# FetController.net
KiCad netlist of a schematic drawn in Altium Designer
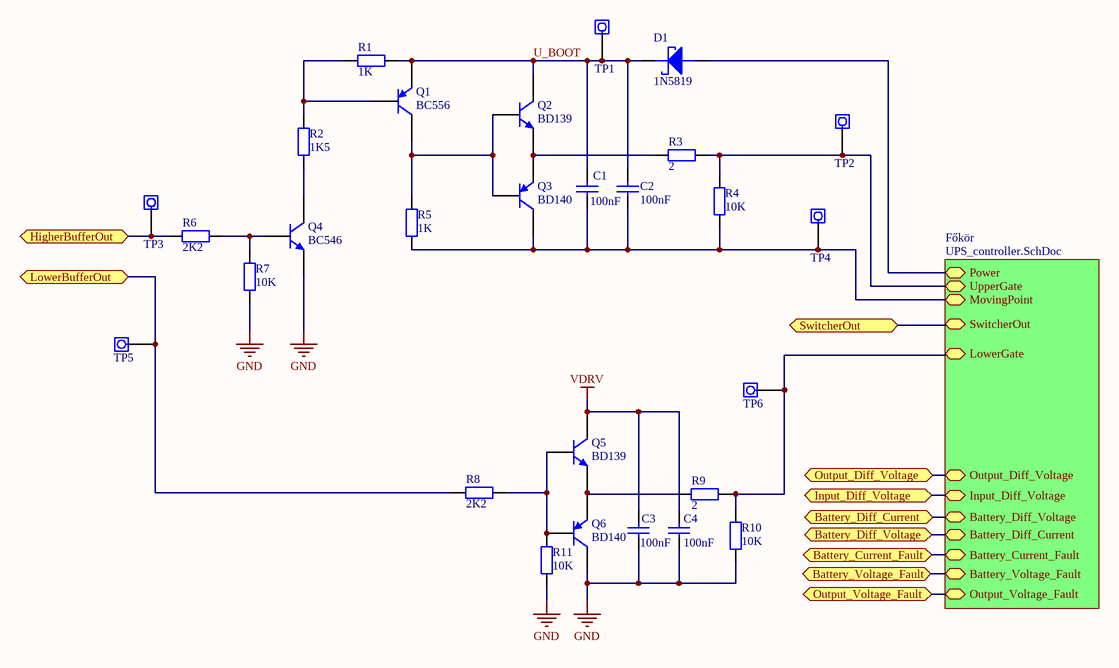
[diagram p0: FetController.SchDoc]

(export (version "E")
  (design (tool "Eeschema 10.0.6"))
  (components
    (comp (ref "C1")
      (value "100nF")
      (footprint "FP_0805_CAP_085")
      (description "Capacitor")
      (libsource (lib "hallglib") (part "CAP"))
    )
    (comp (ref "C2")
      (value "100nF")
      (footprint "FP_0805_CAP_085")
      (description "Capacitor")
      (libsource (lib "hallglib") (part "CAP"))
    )
    (comp (ref "C3")
      (value "100nF")
      (footprint "FP_0805_CAP_085")
      (description "Capacitor")
      (libsource (lib "hallglib") (part "CAP"))
    )
    (comp (ref "C4")
      (value "100nF")
      (footprint "FP_0805_CAP_085")
      (description "Capacitor")
      (libsource (lib "hallglib") (part "CAP"))
    )
    (comp (ref "D1")
      (value "1N5819")
      (footprint "AXIAL-0.3")
      (description "NXP - PMEG3020EJ,115 - SCHOTTKY RECT 30V 2A SOD323F")
      (libsource (lib "hallglib") (part "SCHOTTKY"))
    )
    (comp (ref "Q1")
      (value "BC556")
      (footprint "TO-92")
      (description "PNP tranzisztor")
      (libsource (lib "hallglib") (part "BC556"))
    )
    (comp (ref "Q2")
      (value "BD139")
      (footprint "TO-32")
      (description "NPN tranzisztor")
      (libsource (lib "hallglib") (part "BD139"))
    )
    (comp (ref "Q3")
      (value "BD140")
      (footprint "TO-32")
      (description "PNP tranzisztor")
      (libsource (lib "hallglib") (part "BD140"))
    )
    (comp (ref "Q4")
      (value "BC546")
      (footprint "TO-92")
      (description "NPN tranzisztor")
      (libsource (lib "hallglib") (part "BC546"))
    )
    (comp (ref "Q5")
      (value "BD139")
      (footprint "TO-32")
      (description "NPN tranzisztor")
      (libsource (lib "hallglib") (part "BD139"))
    )
    (comp (ref "Q6")
      (value "BD140")
      (footprint "TO-32")
      (description "PNP tranzisztor")
      (libsource (lib "hallglib") (part "BD140"))
    )
    (comp (ref "R1")
      (value "1K")
      (footprint "AXIAL-0.3")
      (description "Resistor")
      (libsource (lib "") (part "RES_2"))
    )
    (comp (ref "R2")
      (value "1K5")
      (footprint "AXIAL-0.3")
      (description "Resistor")
      (libsource (lib "hallglib") (part "RES"))
    )
    (comp (ref "R3")
      (value "2")
      (footprint "AXIAL-0.3")
      (description "Resistor")
      (libsource (lib "") (part "RES_1"))
    )
    (comp (ref "R4")
      (value "10K")
      (footprint "AXIAL-0.3")
      (description "Resistor")
      (libsource (lib "hallglib") (part "RES"))
    )
    (comp (ref "R5")
      (value "1K")
      (footprint "AXIAL-0.3")
      (description "Resistor")
      (libsource (lib "hallglib") (part "RES"))
    )
    (comp (ref "R6")
      (value "2K2")
      (footprint "AXIAL-0.3")
      (description "Resistor")
      (libsource (lib "") (part "RES_2"))
    )
    (comp (ref "R7")
      (value "10K")
      (footprint "AXIAL-0.3")
      (description "Resistor")
      (libsource (lib "hallglib") (part "RES"))
    )
    (comp (ref "R8")
      (value "2K2")
      (footprint "AXIAL-0.3")
      (description "Resistor")
      (libsource (lib "") (part "RES_2"))
    )
    (comp (ref "R9")
      (value "2")
      (footprint "AXIAL-0.3")
      (description "Resistor")
      (libsource (lib "") (part "RES_1"))
    )
    (comp (ref "R10")
      (value "10K")
      (footprint "AXIAL-0.3")
      (description "Resistor")
      (libsource (lib "hallglib") (part "RES"))
    )
    (comp (ref "R11")
      (value "10K")
      (footprint "AXIAL-0.3")
      (description "Resistor")
      (libsource (lib "hallglib") (part "RES"))
    )
    (comp (ref "TP1")
      (value "Testpoint")
      (footprint "TESTPOINT_1.5")
      (libsource (lib "MERES") (part "Testpoint"))
    )
    (comp (ref "TP2")
      (value "Testpoint")
      (footprint "TESTPOINT_1.5")
      (libsource (lib "MERES") (part "Testpoint"))
    )
    (comp (ref "TP3")
      (value "Testpoint")
      (footprint "TESTPOINT_1.5")
      (libsource (lib "MERES") (part "Testpoint"))
    )
    (comp (ref "TP4")
      (value "Testpoint")
      (footprint "TESTPOINT_1.5")
      (libsource (lib "MERES") (part "Testpoint"))
    )
    (comp (ref "TP5")
      (value "Testpoint")
      (footprint "TESTPOINT_1.5")
      (libsource (lib "MERES") (part "Testpoint"))
    )
    (comp (ref "TP6")
      (value "Testpoint")
      (footprint "TESTPOINT_1.5")
      (libsource (lib "MERES") (part "Testpoint"))
    )
  )
  (nets
    (net (code "5") (name "/HigherBufferOut") (class "Default")
      (node (ref "R6") (pin "2") (pinfunction "2_2") (pintype "passive"))
      (node (ref "TP3") (pin "1") (pinfunction "1_1") (pintype "passive"))
    )
    (net (code "7") (name "/LowerBufferOut") (class "Default")
      (node (ref "R8") (pin "2") (pinfunction "2_2") (pintype "passive"))
      (node (ref "TP5") (pin "1") (pinfunction "1_1") (pintype "passive"))
    )
    (net (code "8") (name "/LowerGate") (class "Default")
      (node (ref "R10") (pin "2") (pinfunction "2_2") (pintype "passive"))
      (node (ref "R9") (pin "2") (pinfunction "2_2") (pintype "passive"))
      (node (ref "TP6") (pin "1") (pinfunction "1_1") (pintype "passive"))
    )
    (net (code "9") (name "/MovingPoint") (class "Default")
      (node (ref "C1") (pin "1") (pinfunction "1_1") (pintype "passive"))
      (node (ref "C2") (pin "1") (pinfunction "1_1") (pintype "passive"))
      (node (ref "Q3") (pin "2") (pinfunction "C_2") (pintype "passive"))
      (node (ref "R4") (pin "1") (pinfunction "1_1") (pintype "passive"))
      (node (ref "R5") (pin "1") (pinfunction "1_1") (pintype "passive"))
      (node (ref "TP4") (pin "1") (pinfunction "1_1") (pintype "passive"))
    )
    (net (code "12") (name "/Power") (class "Default")
      (node (ref "D1") (pin "2") (pinfunction "ANODE_2") (pintype "passive"))
    )
    (net (code "14") (name "/U_BOOT") (class "Default")
      (node (ref "C1") (pin "2") (pinfunction "2_2") (pintype "passive"))
      (node (ref "C2") (pin "2") (pinfunction "2_2") (pintype "passive"))
      (node (ref "D1") (pin "1") (pinfunction "CATHODE_1") (pintype "passive"))
      (node (ref "Q1") (pin "3") (pinfunction "E_3") (pintype "passive"))
      (node (ref "Q2") (pin "2") (pinfunction "C_2") (pintype "passive"))
      (node (ref "R1") (pin "1") (pinfunction "1_1") (pintype "passive"))
      (node (ref "TP1") (pin "1") (pinfunction "1_1") (pintype "passive"))
    )
    (net (code "15") (name "/UpperGate") (class "Default")
      (node (ref "R3") (pin "2") (pinfunction "2_2") (pintype "passive"))
      (node (ref "R4") (pin "2") (pinfunction "2_2") (pintype "passive"))
      (node (ref "TP2") (pin "1") (pinfunction "1_1") (pintype "passive"))
    )
    (net (code "16") (name "GND") (class "Default")
      (node (ref "C3") (pin "1") (pinfunction "1_1") (pintype "passive"))
      (node (ref "C4") (pin "1") (pinfunction "1_1") (pintype "passive"))
      (node (ref "Q4") (pin "3") (pinfunction "E_3") (pintype "passive"))
      (node (ref "Q6") (pin "2") (pinfunction "C_2") (pintype "passive"))
      (node (ref "R10") (pin "1") (pinfunction "1_1") (pintype "passive"))
      (node (ref "R11") (pin "1") (pinfunction "1_1") (pintype "passive"))
      (node (ref "R7") (pin "1") (pinfunction "1_1") (pintype "passive"))
    )
    (net (code "17") (name "Net-(Q1-B)") (class "Default")
      (node (ref "Q1") (pin "2") (pinfunction "B_2") (pintype "passive"))
      (node (ref "R1") (pin "2") (pinfunction "2_2") (pintype "passive"))
      (node (ref "R2") (pin "2") (pinfunction "2_2") (pintype "passive"))
    )
    (net (code "18") (name "Net-(Q1-C)") (class "Default")
      (node (ref "Q1") (pin "1") (pinfunction "C_1") (pintype "passive"))
      (node (ref "Q2") (pin "3") (pinfunction "B_3") (pintype "passive"))
      (node (ref "Q3") (pin "1") (pinfunction "B_1") (pintype "passive"))
      (node (ref "R5") (pin "2") (pinfunction "2_2") (pintype "passive"))
    )
    (net (code "19") (name "Net-(Q2-E)") (class "Default")
      (node (ref "Q2") (pin "1") (pinfunction "E_1") (pintype "passive"))
      (node (ref "Q3") (pin "3") (pinfunction "E_3") (pintype "passive"))
      (node (ref "R3") (pin "1") (pinfunction "1_1") (pintype "passive"))
    )
    (net (code "20") (name "Net-(Q4-B)") (class "Default")
      (node (ref "Q4") (pin "2") (pinfunction "B_2") (pintype "passive"))
      (node (ref "R6") (pin "1") (pinfunction "1_1") (pintype "passive"))
      (node (ref "R7") (pin "2") (pinfunction "2_2") (pintype "passive"))
    )
    (net (code "21") (name "Net-(Q4-C)") (class "Default")
      (node (ref "Q4") (pin "1") (pinfunction "C_1") (pintype "passive"))
      (node (ref "R2") (pin "1") (pinfunction "1_1") (pintype "passive"))
    )
    (net (code "22") (name "Net-(Q5-B)") (class "Default")
      (node (ref "Q5") (pin "3") (pinfunction "B_3") (pintype "passive"))
      (node (ref "Q6") (pin "1") (pinfunction "B_1") (pintype "passive"))
      (node (ref "R11") (pin "2") (pinfunction "2_2") (pintype "passive"))
      (node (ref "R8") (pin "1") (pinfunction "1_1") (pintype "passive"))
    )
    (net (code "23") (name "Net-(Q5-E)") (class "Default")
      (node (ref "Q5") (pin "1") (pinfunction "E_1") (pintype "passive"))
      (node (ref "Q6") (pin "3") (pinfunction "E_3") (pintype "passive"))
      (node (ref "R9") (pin "1") (pinfunction "1_1") (pintype "passive"))
    )
    (net (code "24") (name "VDRV") (class "Default")
      (node (ref "C3") (pin "2") (pinfunction "2_2") (pintype "passive"))
      (node (ref "C4") (pin "2") (pinfunction "2_2") (pintype "passive"))
      (node (ref "Q5") (pin "2") (pinfunction "C_2") (pintype "passive"))
    )
  )
)
